# tiny1624.net
KiCad netlist of a schematic drawn in EAGLE
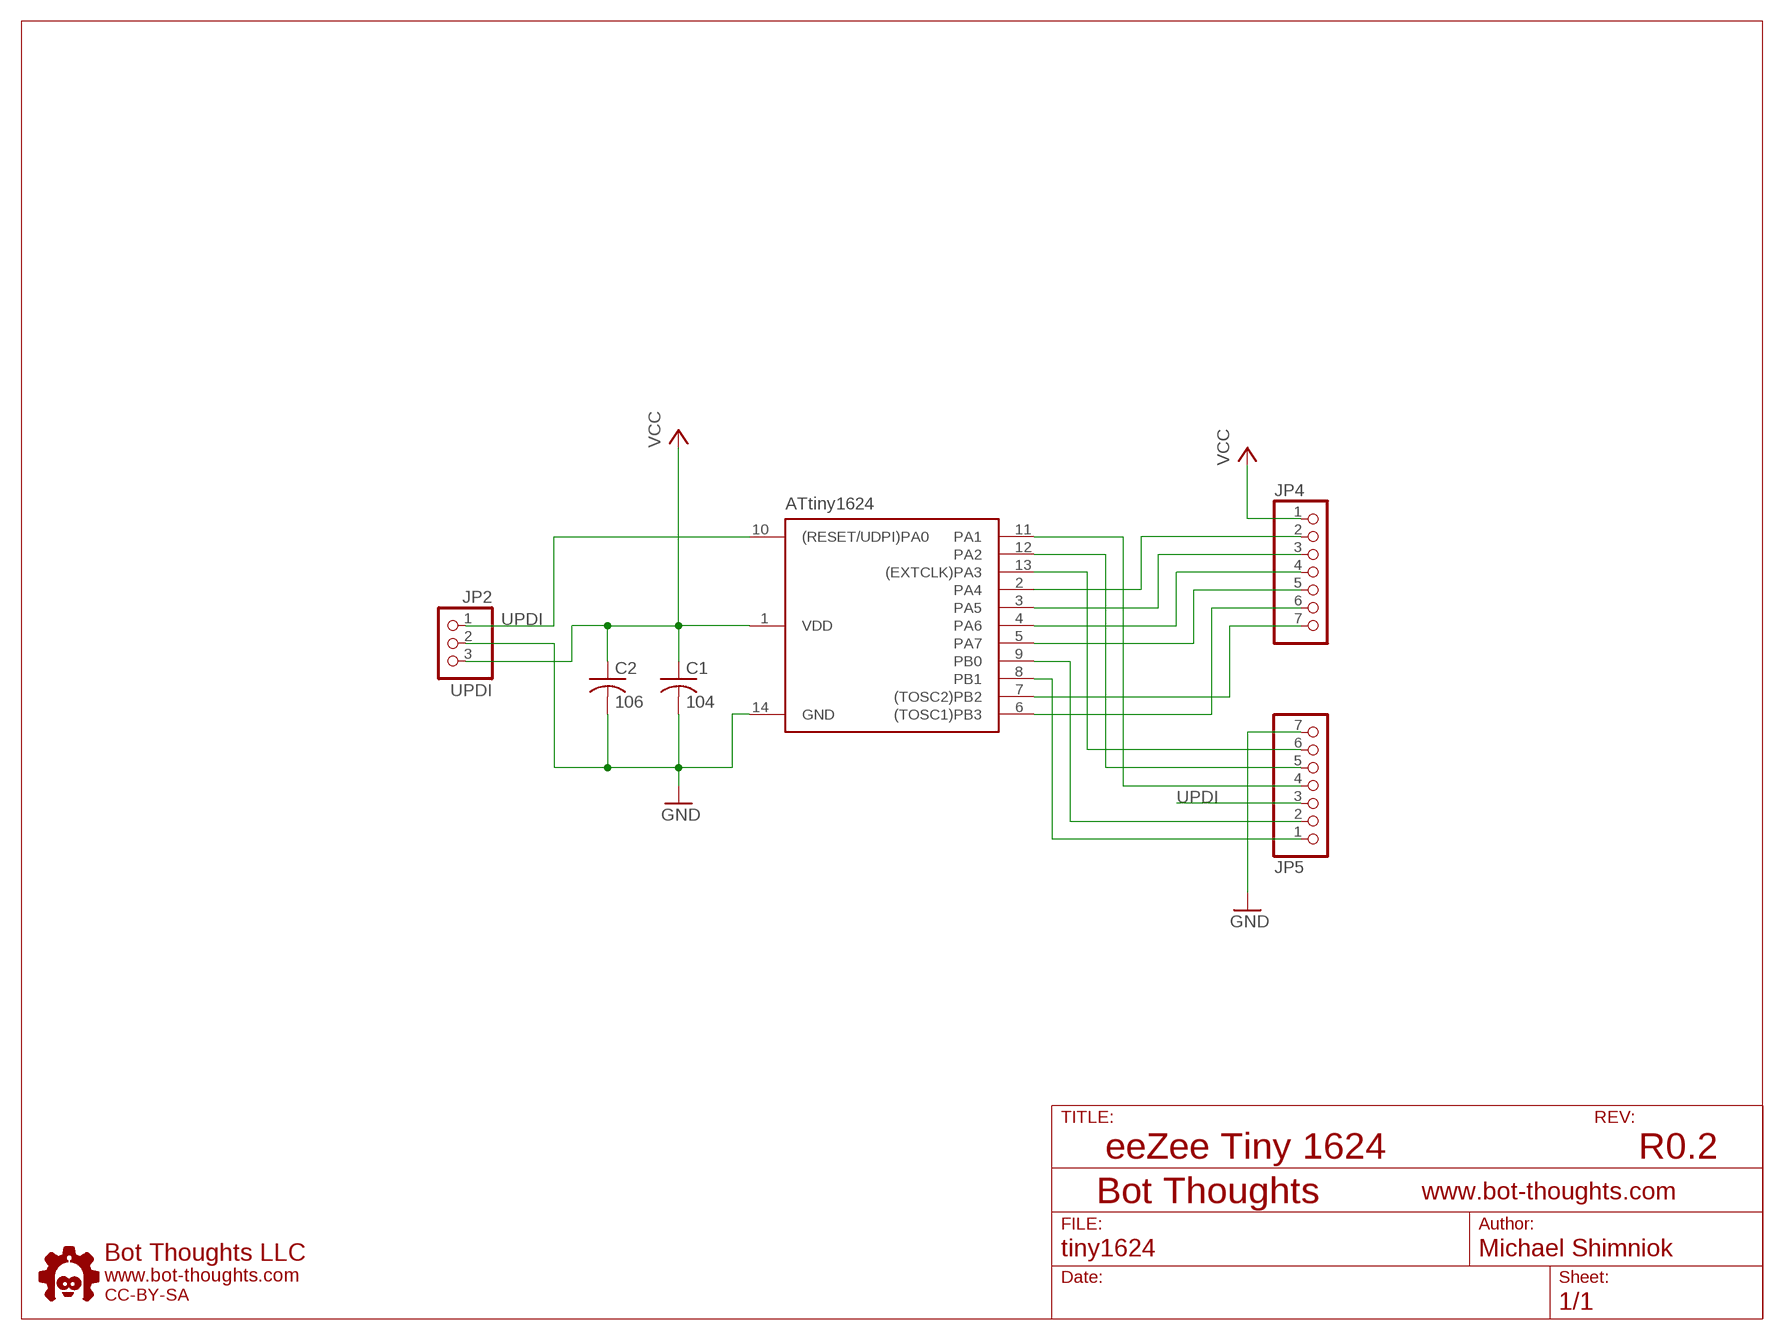
[diagram p0: schematic, sheet 1]

(export (version "E")
  (design (tool "Eeschema 10.0.6"))
  (components
    (comp (ref "C1")
      (value "104")
      (footprint "eagle-import:C0603")
      (fields (field (name "PARTNO") "0603YC104KAT2A"))
      (libsource (lib "eagle-import") (part "C-USC0603"))
    )
    (comp (ref "C2")
      (value "106")
      (footprint "eagle-import:1206")
      (fields (field (name "PARTNO") "MCTT21X106M6R3CT"))
      (libsource (lib "eagle-import") (part "C-1206"))
    )
    (comp (ref "JP2")
      (value "UPDI")
      (footprint "eagle-import:1X03-S")
      (libsource (lib "eagle-import") (part "PINHD-1X03_2.54-S"))
    )
    (comp (ref "JP4")
      (value "PINHD-1X07_2.54-S")
      (footprint "eagle-import:1X07-S")
      (libsource (lib "eagle-import") (part "PINHD-1X07_2.54-S"))
    )
    (comp (ref "JP5")
      (value "PINHD-1X07_2.54-S")
      (footprint "eagle-import:1X07-S")
      (libsource (lib "eagle-import") (part "PINHD-1X07_2.54-S"))
    )
    (comp (ref "U$1")
      (value "BTLOGO-LOGO-MD")
      (footprint "eagle-import:BTLOGOM")
      (libsource (lib "eagle-import") (part "BTLOGO-LOGO-MD"))
    )
    (comp (ref "U1")
      (value "ATTINY1624")
      (footprint "eagle-import:SOIC14N")
      (libsource (lib "eagle-import") (part "ATTINY1624-SSU"))
    )
  )
  (nets
    (net (code "1") (name "/UPDI") (class "Default")
      (node (ref "JP2") (pin "1") (pinfunction "1_1") (pintype "passive"))
      (node (ref "JP5") (pin "3") (pinfunction "3_3") (pintype "passive"))
      (node (ref "U1") (pin "10") (pinfunction "(RESET/UDPI)PA0_10") (pintype "bidirectional"))
    )
    (net (code "2") (name "GND") (class "Default")
      (node (ref "C1") (pin "2") (pinfunction "2_2") (pintype "passive"))
      (node (ref "C2") (pin "2") (pinfunction "-_2") (pintype "passive"))
      (node (ref "JP2") (pin "2") (pinfunction "2_2") (pintype "passive"))
      (node (ref "JP5") (pin "7") (pinfunction "7_7") (pintype "passive"))
      (node (ref "U1") (pin "14") (pinfunction "GND_14") (pintype "power_in"))
    )
    (net (code "3") (name "Net-(U1-(EXTCLK)PA3)") (class "Default")
      (node (ref "JP5") (pin "6") (pinfunction "6_6") (pintype "passive"))
      (node (ref "U1") (pin "13") (pinfunction "(EXTCLK)PA3_13") (pintype "bidirectional"))
    )
    (net (code "4") (name "Net-(U1-(TOSC1)PB3)") (class "Default")
      (node (ref "JP4") (pin "6") (pinfunction "6_6") (pintype "passive"))
      (node (ref "U1") (pin "6") (pinfunction "(TOSC1)PB3_6") (pintype "bidirectional"))
    )
    (net (code "5") (name "Net-(U1-(TOSC2)PB2)") (class "Default")
      (node (ref "JP4") (pin "7") (pinfunction "7_7") (pintype "passive"))
      (node (ref "U1") (pin "7") (pinfunction "(TOSC2)PB2_7") (pintype "bidirectional"))
    )
    (net (code "6") (name "Net-(U1-PA1)") (class "Default")
      (node (ref "JP5") (pin "4") (pinfunction "4_4") (pintype "passive"))
      (node (ref "U1") (pin "11") (pinfunction "PA1_11") (pintype "bidirectional"))
    )
    (net (code "7") (name "Net-(U1-PA2)") (class "Default")
      (node (ref "JP5") (pin "5") (pinfunction "5_5") (pintype "passive"))
      (node (ref "U1") (pin "12") (pinfunction "PA2_12") (pintype "bidirectional"))
    )
    (net (code "8") (name "Net-(U1-PA4)") (class "Default")
      (node (ref "JP4") (pin "2") (pinfunction "2_2") (pintype "passive"))
      (node (ref "U1") (pin "2") (pinfunction "PA4_2") (pintype "bidirectional"))
    )
    (net (code "9") (name "Net-(U1-PA5)") (class "Default")
      (node (ref "JP4") (pin "3") (pinfunction "3_3") (pintype "passive"))
      (node (ref "U1") (pin "3") (pinfunction "PA5_3") (pintype "bidirectional"))
    )
    (net (code "10") (name "Net-(U1-PA6)") (class "Default")
      (node (ref "JP4") (pin "4") (pinfunction "4_4") (pintype "passive"))
      (node (ref "U1") (pin "4") (pinfunction "PA6_4") (pintype "bidirectional"))
    )
    (net (code "11") (name "Net-(U1-PA7)") (class "Default")
      (node (ref "JP4") (pin "5") (pinfunction "5_5") (pintype "passive"))
      (node (ref "U1") (pin "5") (pinfunction "PA7_5") (pintype "bidirectional"))
    )
    (net (code "12") (name "Net-(U1-PB0)") (class "Default")
      (node (ref "JP5") (pin "2") (pinfunction "2_2") (pintype "passive"))
      (node (ref "U1") (pin "9") (pinfunction "PB0_9") (pintype "bidirectional"))
    )
    (net (code "13") (name "Net-(U1-PB1)") (class "Default")
      (node (ref "JP5") (pin "1") (pinfunction "1_1") (pintype "passive"))
      (node (ref "U1") (pin "8") (pinfunction "PB1_8") (pintype "bidirectional"))
    )
    (net (code "14") (name "VCC") (class "Default")
      (node (ref "C1") (pin "1") (pinfunction "1_1") (pintype "passive"))
      (node (ref "C2") (pin "1") (pinfunction "+_1") (pintype "passive"))
      (node (ref "JP2") (pin "3") (pinfunction "3_3") (pintype "passive"))
      (node (ref "JP4") (pin "1") (pinfunction "1_1") (pintype "passive"))
      (node (ref "U1") (pin "1") (pinfunction "VDD_1") (pintype "power_in"))
    )
  )
)
